# 002.net
KiCad netlist of a schematic drawn in EAGLE
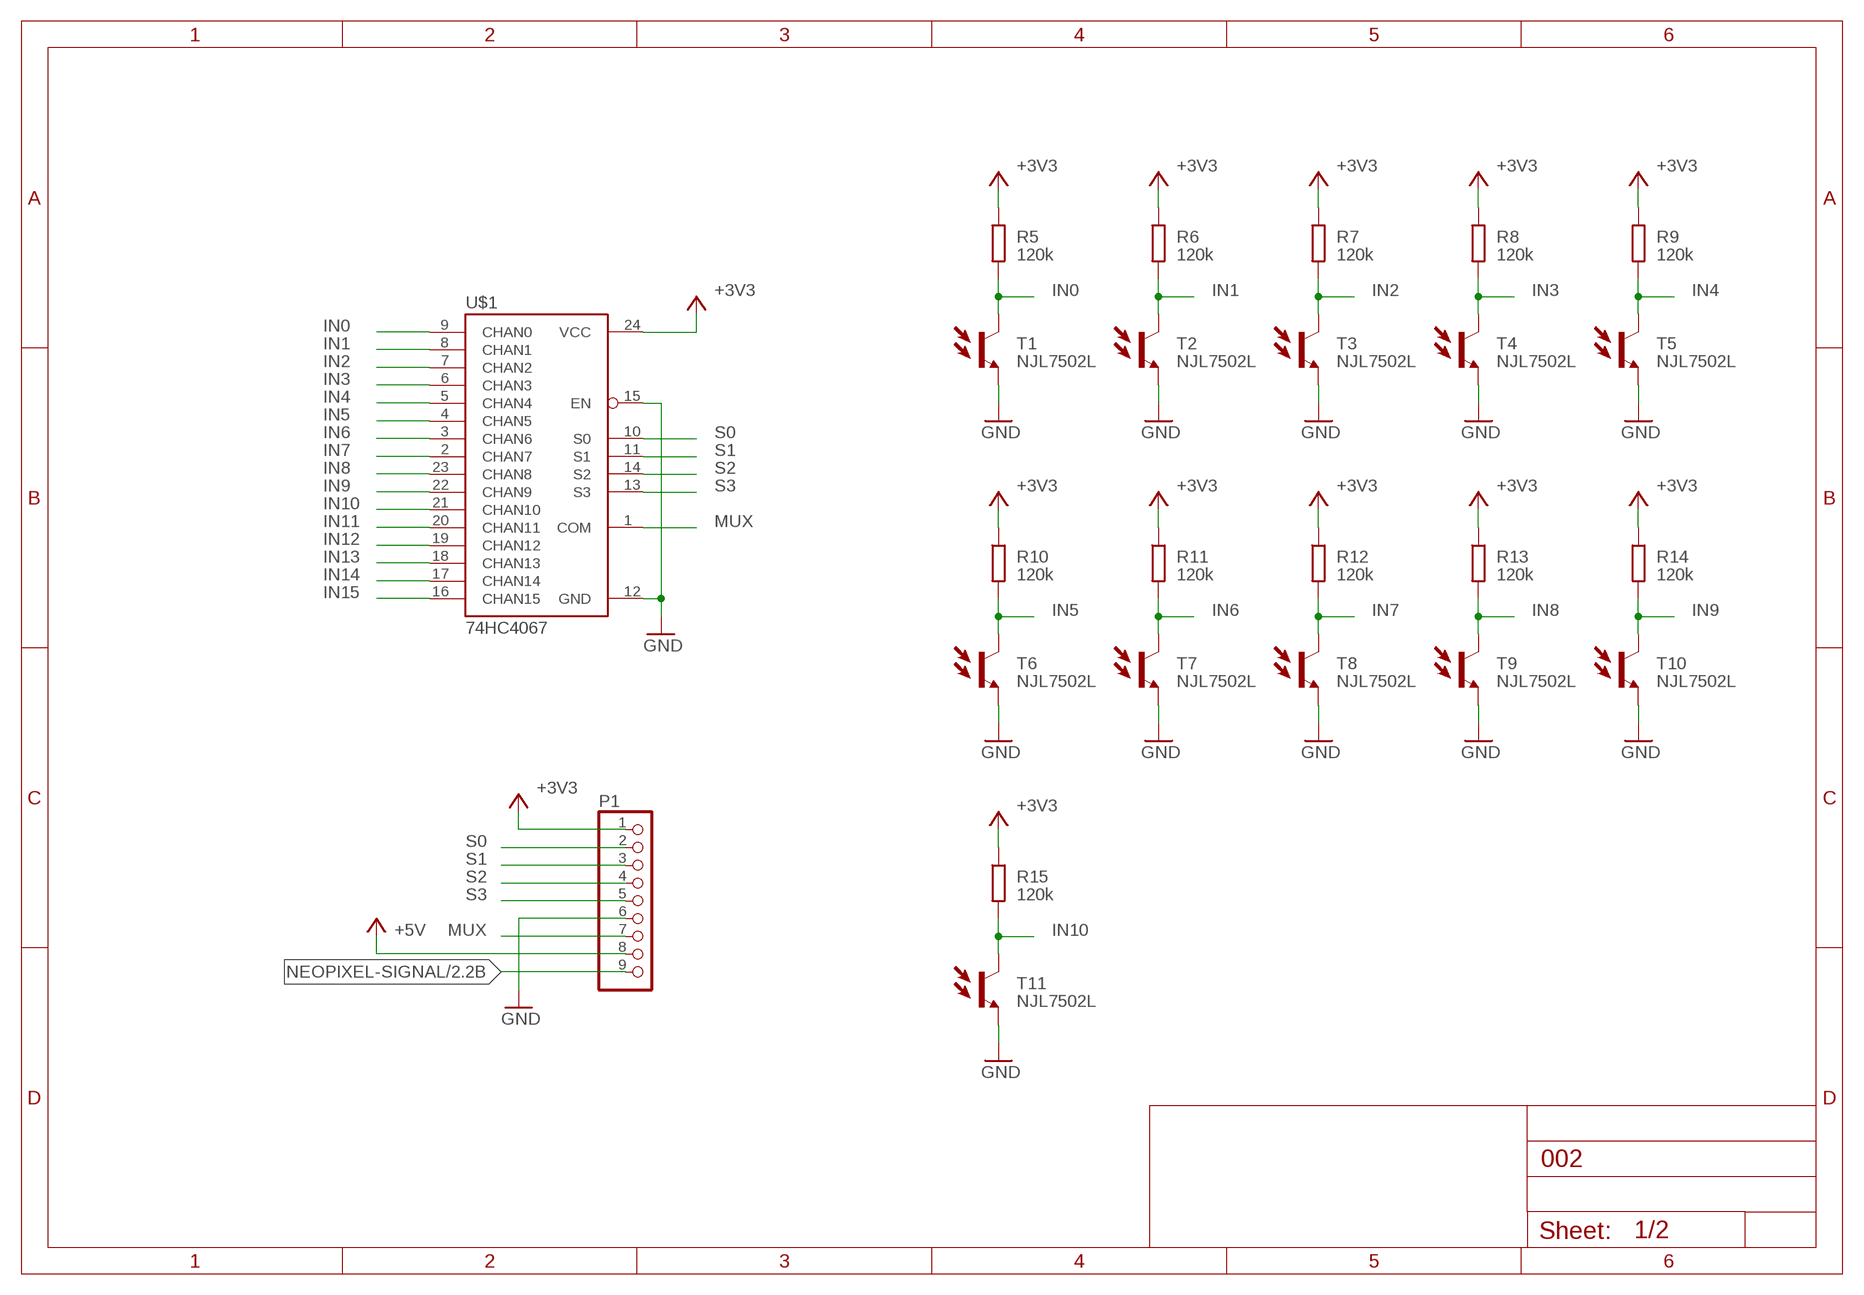
[diagram p0: schematic, sheet 1]
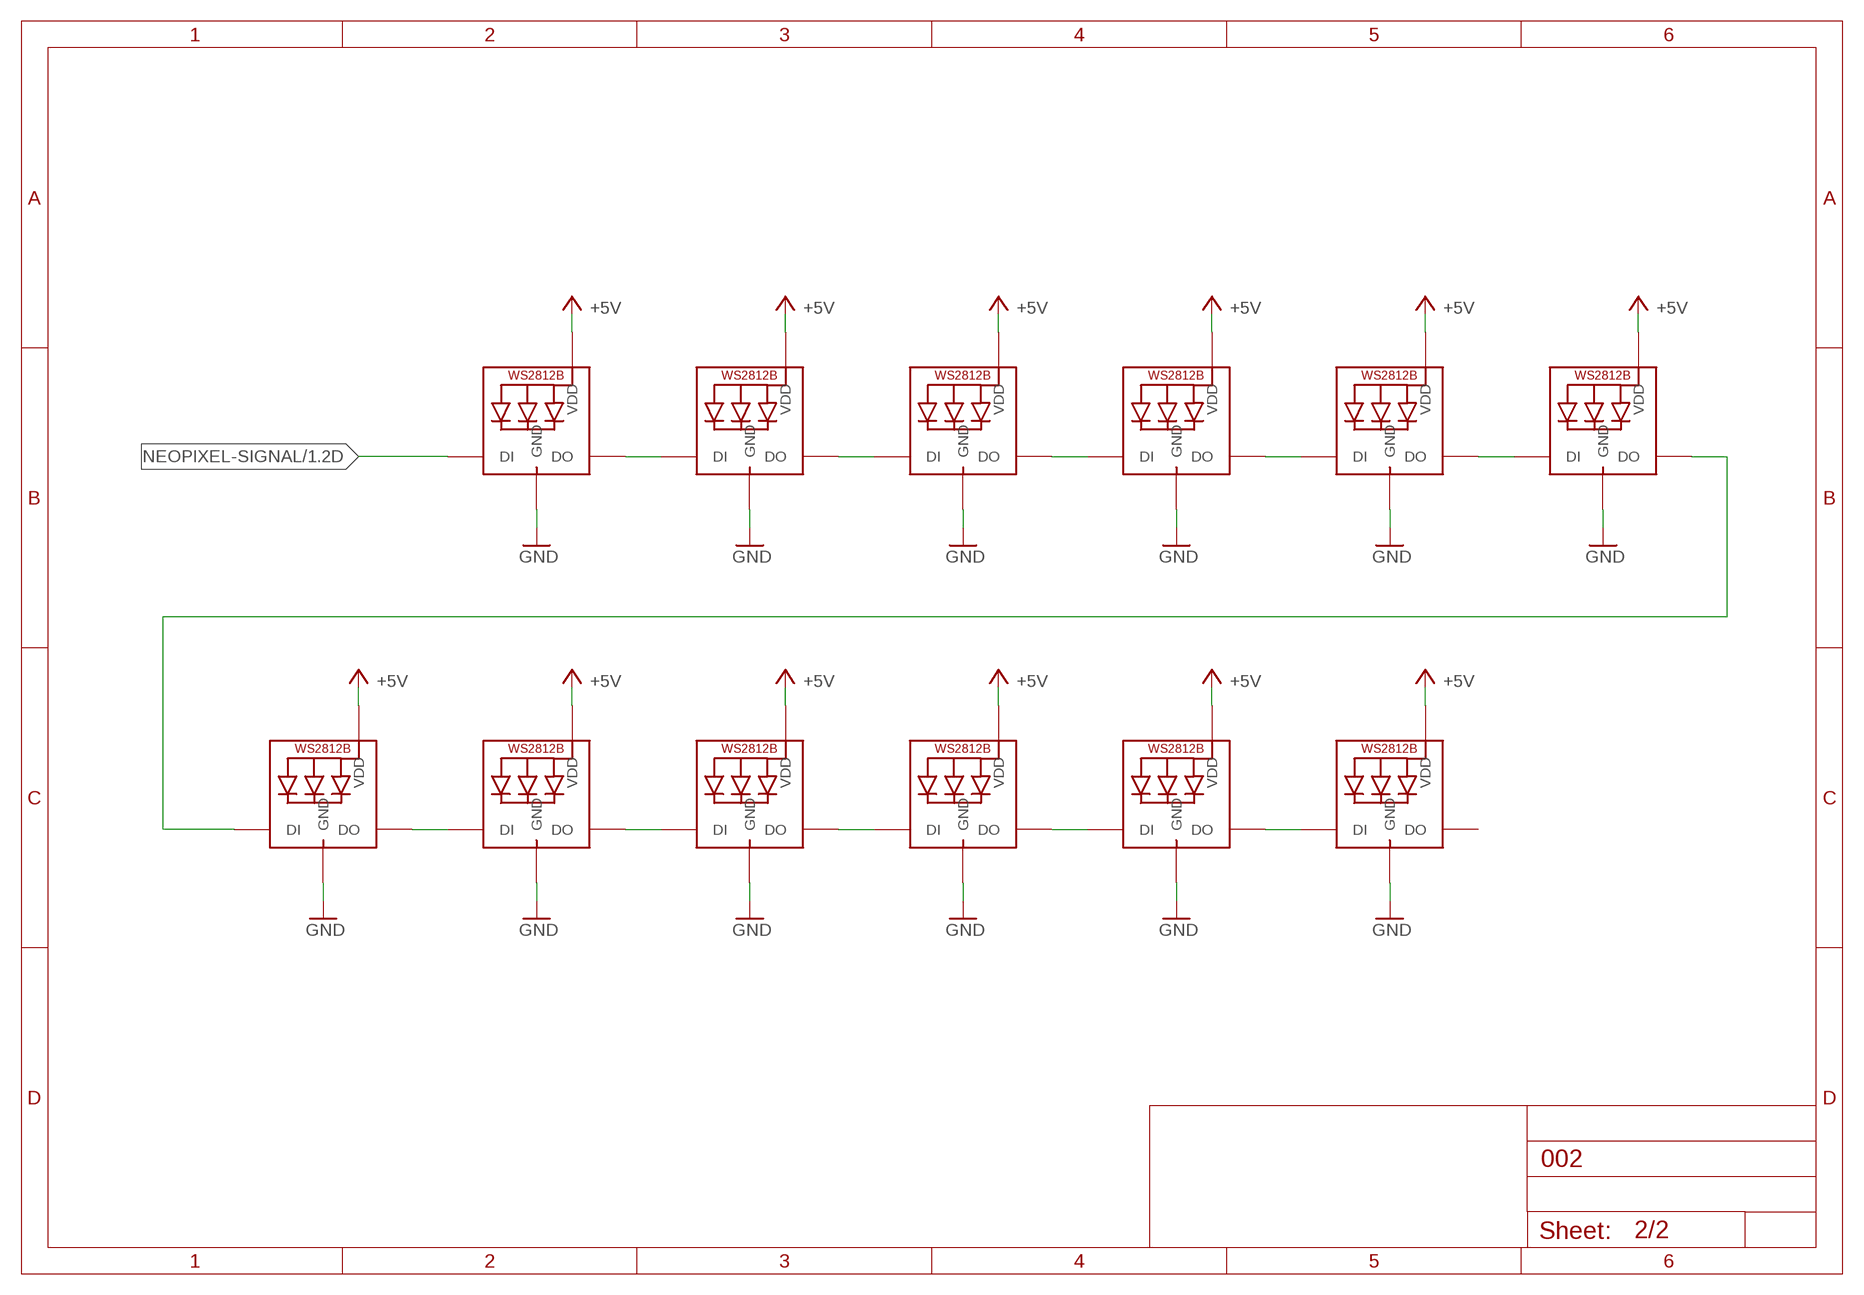
[diagram p1: schematic, sheet 2]

(export (version "E")
  (design (tool "Eeschema 10.0.6"))
  (components
    (comp (ref "LED1")
      (value "WS2812B5050")
      (footprint "eagle-import:WS2812B")
      (libsource (lib "eagle-import") (part "WS2812B5050"))
    )
    (comp (ref "LED2")
      (value "WS2812B5050")
      (footprint "eagle-import:WS2812B")
      (libsource (lib "eagle-import") (part "WS2812B5050"))
    )
    (comp (ref "LED3")
      (value "WS2812B5050")
      (footprint "eagle-import:WS2812B")
      (libsource (lib "eagle-import") (part "WS2812B5050"))
    )
    (comp (ref "LED4")
      (value "WS2812B5050")
      (footprint "eagle-import:WS2812B")
      (libsource (lib "eagle-import") (part "WS2812B5050"))
    )
    (comp (ref "LED5")
      (value "WS2812B5050")
      (footprint "eagle-import:WS2812B")
      (libsource (lib "eagle-import") (part "WS2812B5050"))
    )
    (comp (ref "LED6")
      (value "WS2812B5050")
      (footprint "eagle-import:WS2812B")
      (libsource (lib "eagle-import") (part "WS2812B5050"))
    )
    (comp (ref "LED7")
      (value "WS2812B5050")
      (footprint "eagle-import:WS2812B")
      (libsource (lib "eagle-import") (part "WS2812B5050"))
    )
    (comp (ref "LED8")
      (value "WS2812B5050")
      (footprint "eagle-import:WS2812B")
      (libsource (lib "eagle-import") (part "WS2812B5050"))
    )
    (comp (ref "LED9")
      (value "WS2812B5050")
      (footprint "eagle-import:WS2812B")
      (libsource (lib "eagle-import") (part "WS2812B5050"))
    )
    (comp (ref "LED10")
      (value "WS2812B5050")
      (footprint "eagle-import:WS2812B")
      (libsource (lib "eagle-import") (part "WS2812B5050"))
    )
    (comp (ref "LED11")
      (value "WS2812B5050")
      (footprint "eagle-import:WS2812B")
      (libsource (lib "eagle-import") (part "WS2812B5050"))
    )
    (comp (ref "LED12")
      (value "WS2812B5050")
      (footprint "eagle-import:WS2812B")
      (libsource (lib "eagle-import") (part "WS2812B5050"))
    )
    (comp (ref "P1")
      (value "S9B-ZR-SM4A-TF")
      (footprint "eagle-import:ZH-SM4-SIDE09")
      (libsource (lib "eagle-import") (part "S9B-ZR-SM4A-TF"))
    )
    (comp (ref "R5")
      (value "120k")
      (footprint "eagle-import:R0805")
      (libsource (lib "eagle-import") (part "R-EU_R0805"))
    )
    (comp (ref "R6")
      (value "120k")
      (footprint "eagle-import:R0805")
      (libsource (lib "eagle-import") (part "R-EU_R0805"))
    )
    (comp (ref "R7")
      (value "120k")
      (footprint "eagle-import:R0805")
      (libsource (lib "eagle-import") (part "R-EU_R0805"))
    )
    (comp (ref "R8")
      (value "120k")
      (footprint "eagle-import:R0805")
      (libsource (lib "eagle-import") (part "R-EU_R0805"))
    )
    (comp (ref "R9")
      (value "120k")
      (footprint "eagle-import:R0805")
      (libsource (lib "eagle-import") (part "R-EU_R0805"))
    )
    (comp (ref "R10")
      (value "120k")
      (footprint "eagle-import:R0805")
      (libsource (lib "eagle-import") (part "R-EU_R0805"))
    )
    (comp (ref "R11")
      (value "120k")
      (footprint "eagle-import:R0805")
      (libsource (lib "eagle-import") (part "R-EU_R0805"))
    )
    (comp (ref "R12")
      (value "120k")
      (footprint "eagle-import:R0805")
      (libsource (lib "eagle-import") (part "R-EU_R0805"))
    )
    (comp (ref "R13")
      (value "120k")
      (footprint "eagle-import:R0805")
      (libsource (lib "eagle-import") (part "R-EU_R0805"))
    )
    (comp (ref "R14")
      (value "120k")
      (footprint "eagle-import:R0805")
      (libsource (lib "eagle-import") (part "R-EU_R0805"))
    )
    (comp (ref "R15")
      (value "120k")
      (footprint "eagle-import:R0805")
      (libsource (lib "eagle-import") (part "R-EU_R0805"))
    )
    (comp (ref "T1")
      (value "NJL7502L")
      (footprint "eagle-import:MYPARTS_NJL7502L")
      (libsource (lib "eagle-import") (part "MYPARTS_NJL7502L"))
    )
    (comp (ref "T2")
      (value "NJL7502L")
      (footprint "eagle-import:MYPARTS_NJL7502L")
      (libsource (lib "eagle-import") (part "MYPARTS_NJL7502L"))
    )
    (comp (ref "T3")
      (value "NJL7502L")
      (footprint "eagle-import:MYPARTS_NJL7502L")
      (libsource (lib "eagle-import") (part "MYPARTS_NJL7502L"))
    )
    (comp (ref "T4")
      (value "NJL7502L")
      (footprint "eagle-import:MYPARTS_NJL7502L")
      (libsource (lib "eagle-import") (part "MYPARTS_NJL7502L"))
    )
    (comp (ref "T5")
      (value "NJL7502L")
      (footprint "eagle-import:MYPARTS_NJL7502L")
      (libsource (lib "eagle-import") (part "MYPARTS_NJL7502L"))
    )
    (comp (ref "T6")
      (value "NJL7502L")
      (footprint "eagle-import:MYPARTS_NJL7502L")
      (libsource (lib "eagle-import") (part "MYPARTS_NJL7502L"))
    )
    (comp (ref "T7")
      (value "NJL7502L")
      (footprint "eagle-import:MYPARTS_NJL7502L")
      (libsource (lib "eagle-import") (part "MYPARTS_NJL7502L"))
    )
    (comp (ref "T8")
      (value "NJL7502L")
      (footprint "eagle-import:MYPARTS_NJL7502L")
      (libsource (lib "eagle-import") (part "MYPARTS_NJL7502L"))
    )
    (comp (ref "T9")
      (value "NJL7502L")
      (footprint "eagle-import:MYPARTS_NJL7502L")
      (libsource (lib "eagle-import") (part "MYPARTS_NJL7502L"))
    )
    (comp (ref "T10")
      (value "NJL7502L")
      (footprint "eagle-import:MYPARTS_NJL7502L")
      (libsource (lib "eagle-import") (part "MYPARTS_NJL7502L"))
    )
    (comp (ref "T11")
      (value "NJL7502L")
      (footprint "eagle-import:MYPARTS_NJL7502L")
      (libsource (lib "eagle-import") (part "MYPARTS_NJL7502L"))
    )
    (comp (ref "U$1")
      (value "74HC4067")
      (footprint "eagle-import:SPARKFUN_SSOP24")
      (libsource (lib "eagle-import") (part "SPARKFUN_MUX-74HC4067SMD"))
    )
  )
  (nets
    (net (code "1") (name "+3V3") (class "Default")
      (node (ref "P1") (pin "1") (pinfunction "1_1") (pintype "passive"))
      (node (ref "R10") (pin "1") (pinfunction "1_1") (pintype "passive"))
      (node (ref "R11") (pin "1") (pinfunction "1_1") (pintype "passive"))
      (node (ref "R12") (pin "1") (pinfunction "1_1") (pintype "passive"))
      (node (ref "R13") (pin "1") (pinfunction "1_1") (pintype "passive"))
      (node (ref "R14") (pin "1") (pinfunction "1_1") (pintype "passive"))
      (node (ref "R15") (pin "1") (pinfunction "1_1") (pintype "passive"))
      (node (ref "R5") (pin "1") (pinfunction "1_1") (pintype "passive"))
      (node (ref "R6") (pin "1") (pinfunction "1_1") (pintype "passive"))
      (node (ref "R7") (pin "1") (pinfunction "1_1") (pintype "passive"))
      (node (ref "R8") (pin "1") (pinfunction "1_1") (pintype "passive"))
      (node (ref "R9") (pin "1") (pinfunction "1_1") (pintype "passive"))
      (node (ref "U$1") (pin "24") (pinfunction "VCC_24") (pintype "bidirectional"))
    )
    (net (code "2") (name "+5V") (class "Default")
      (node (ref "LED1") (pin "1-VDD") (pinfunction "VDD_1-VDD") (pintype "power_in"))
      (node (ref "LED10") (pin "1-VDD") (pinfunction "VDD_1-VDD") (pintype "power_in"))
      (node (ref "LED11") (pin "1-VDD") (pinfunction "VDD_1-VDD") (pintype "power_in"))
      (node (ref "LED12") (pin "1-VDD") (pinfunction "VDD_1-VDD") (pintype "power_in"))
      (node (ref "LED2") (pin "1-VDD") (pinfunction "VDD_1-VDD") (pintype "power_in"))
      (node (ref "LED3") (pin "1-VDD") (pinfunction "VDD_1-VDD") (pintype "power_in"))
      (node (ref "LED4") (pin "1-VDD") (pinfunction "VDD_1-VDD") (pintype "power_in"))
      (node (ref "LED5") (pin "1-VDD") (pinfunction "VDD_1-VDD") (pintype "power_in"))
      (node (ref "LED6") (pin "1-VDD") (pinfunction "VDD_1-VDD") (pintype "power_in"))
      (node (ref "LED7") (pin "1-VDD") (pinfunction "VDD_1-VDD") (pintype "power_in"))
      (node (ref "LED8") (pin "1-VDD") (pinfunction "VDD_1-VDD") (pintype "power_in"))
      (node (ref "LED9") (pin "1-VDD") (pinfunction "VDD_1-VDD") (pintype "power_in"))
      (node (ref "P1") (pin "8") (pinfunction "8_8") (pintype "passive"))
    )
    (net (code "3") (name "GND") (class "Default")
      (node (ref "LED1") (pin "3-GND") (pinfunction "GND_3-GND") (pintype "power_in"))
      (node (ref "LED10") (pin "3-GND") (pinfunction "GND_3-GND") (pintype "power_in"))
      (node (ref "LED11") (pin "3-GND") (pinfunction "GND_3-GND") (pintype "power_in"))
      (node (ref "LED12") (pin "3-GND") (pinfunction "GND_3-GND") (pintype "power_in"))
      (node (ref "LED2") (pin "3-GND") (pinfunction "GND_3-GND") (pintype "power_in"))
      (node (ref "LED3") (pin "3-GND") (pinfunction "GND_3-GND") (pintype "power_in"))
      (node (ref "LED4") (pin "3-GND") (pinfunction "GND_3-GND") (pintype "power_in"))
      (node (ref "LED5") (pin "3-GND") (pinfunction "GND_3-GND") (pintype "power_in"))
      (node (ref "LED6") (pin "3-GND") (pinfunction "GND_3-GND") (pintype "power_in"))
      (node (ref "LED7") (pin "3-GND") (pinfunction "GND_3-GND") (pintype "power_in"))
      (node (ref "LED8") (pin "3-GND") (pinfunction "GND_3-GND") (pintype "power_in"))
      (node (ref "LED9") (pin "3-GND") (pinfunction "GND_3-GND") (pintype "power_in"))
      (node (ref "P1") (pin "6") (pinfunction "6_6") (pintype "passive"))
      (node (ref "T1") (pin "E") (pinfunction "E_E") (pintype "passive"))
      (node (ref "T10") (pin "E") (pinfunction "E_E") (pintype "passive"))
      (node (ref "T11") (pin "E") (pinfunction "E_E") (pintype "passive"))
      (node (ref "T2") (pin "E") (pinfunction "E_E") (pintype "passive"))
      (node (ref "T3") (pin "E") (pinfunction "E_E") (pintype "passive"))
      (node (ref "T4") (pin "E") (pinfunction "E_E") (pintype "passive"))
      (node (ref "T5") (pin "E") (pinfunction "E_E") (pintype "passive"))
      (node (ref "T6") (pin "E") (pinfunction "E_E") (pintype "passive"))
      (node (ref "T7") (pin "E") (pinfunction "E_E") (pintype "passive"))
      (node (ref "T8") (pin "E") (pinfunction "E_E") (pintype "passive"))
      (node (ref "T9") (pin "E") (pinfunction "E_E") (pintype "passive"))
      (node (ref "U$1") (pin "12") (pinfunction "GND_12") (pintype "bidirectional"))
      (node (ref "U$1") (pin "15") (pinfunction "EN_15") (pintype "input"))
    )
    (net (code "4") (name "IN0") (class "Default")
      (node (ref "R5") (pin "2") (pinfunction "2_2") (pintype "passive"))
      (node (ref "T1") (pin "C") (pinfunction "C_C") (pintype "passive"))
      (node (ref "U$1") (pin "9") (pinfunction "CHAN0_9") (pintype "bidirectional"))
    )
    (net (code "5") (name "IN1") (class "Default")
      (node (ref "R6") (pin "2") (pinfunction "2_2") (pintype "passive"))
      (node (ref "T2") (pin "C") (pinfunction "C_C") (pintype "passive"))
      (node (ref "U$1") (pin "8") (pinfunction "CHAN1_8") (pintype "bidirectional"))
    )
    (net (code "6") (name "IN2") (class "Default")
      (node (ref "R7") (pin "2") (pinfunction "2_2") (pintype "passive"))
      (node (ref "T3") (pin "C") (pinfunction "C_C") (pintype "passive"))
      (node (ref "U$1") (pin "7") (pinfunction "CHAN2_7") (pintype "bidirectional"))
    )
    (net (code "7") (name "IN3") (class "Default")
      (node (ref "R8") (pin "2") (pinfunction "2_2") (pintype "passive"))
      (node (ref "T4") (pin "C") (pinfunction "C_C") (pintype "passive"))
      (node (ref "U$1") (pin "6") (pinfunction "CHAN3_6") (pintype "bidirectional"))
    )
    (net (code "8") (name "IN4") (class "Default")
      (node (ref "R9") (pin "2") (pinfunction "2_2") (pintype "passive"))
      (node (ref "T5") (pin "C") (pinfunction "C_C") (pintype "passive"))
      (node (ref "U$1") (pin "5") (pinfunction "CHAN4_5") (pintype "bidirectional"))
    )
    (net (code "9") (name "IN5") (class "Default")
      (node (ref "R10") (pin "2") (pinfunction "2_2") (pintype "passive"))
      (node (ref "T6") (pin "C") (pinfunction "C_C") (pintype "passive"))
      (node (ref "U$1") (pin "4") (pinfunction "CHAN5_4") (pintype "bidirectional"))
    )
    (net (code "10") (name "IN6") (class "Default")
      (node (ref "R11") (pin "2") (pinfunction "2_2") (pintype "passive"))
      (node (ref "T7") (pin "C") (pinfunction "C_C") (pintype "passive"))
      (node (ref "U$1") (pin "3") (pinfunction "CHAN6_3") (pintype "bidirectional"))
    )
    (net (code "11") (name "IN7") (class "Default")
      (node (ref "R12") (pin "2") (pinfunction "2_2") (pintype "passive"))
      (node (ref "T8") (pin "C") (pinfunction "C_C") (pintype "passive"))
      (node (ref "U$1") (pin "2") (pinfunction "CHAN7_2") (pintype "bidirectional"))
    )
    (net (code "12") (name "IN8") (class "Default")
      (node (ref "R13") (pin "2") (pinfunction "2_2") (pintype "passive"))
      (node (ref "T9") (pin "C") (pinfunction "C_C") (pintype "passive"))
      (node (ref "U$1") (pin "23") (pinfunction "CHAN8_23") (pintype "bidirectional"))
    )
    (net (code "13") (name "IN9") (class "Default")
      (node (ref "R14") (pin "2") (pinfunction "2_2") (pintype "passive"))
      (node (ref "T10") (pin "C") (pinfunction "C_C") (pintype "passive"))
      (node (ref "U$1") (pin "22") (pinfunction "CHAN9_22") (pintype "bidirectional"))
    )
    (net (code "14") (name "IN10") (class "Default")
      (node (ref "R15") (pin "2") (pinfunction "2_2") (pintype "passive"))
      (node (ref "T11") (pin "C") (pinfunction "C_C") (pintype "passive"))
      (node (ref "U$1") (pin "21") (pinfunction "CHAN10_21") (pintype "bidirectional"))
    )
    (net (code "15") (name "IN11") (class "Default")
      (node (ref "U$1") (pin "20") (pinfunction "CHAN11_20") (pintype "bidirectional"))
    )
    (net (code "16") (name "IN12") (class "Default")
      (node (ref "U$1") (pin "19") (pinfunction "CHAN12_19") (pintype "bidirectional"))
    )
    (net (code "17") (name "IN13") (class "Default")
      (node (ref "U$1") (pin "18") (pinfunction "CHAN13_18") (pintype "bidirectional"))
    )
    (net (code "18") (name "IN14") (class "Default")
      (node (ref "U$1") (pin "17") (pinfunction "CHAN14_17") (pintype "bidirectional"))
    )
    (net (code "19") (name "IN15") (class "Default")
      (node (ref "U$1") (pin "16") (pinfunction "CHAN15_16") (pintype "bidirectional"))
    )
    (net (code "20") (name "MUX") (class "Default")
      (node (ref "P1") (pin "7") (pinfunction "7_7") (pintype "passive"))
      (node (ref "U$1") (pin "1") (pinfunction "COM_1") (pintype "bidirectional"))
    )
    (net (code "21") (name "NEOPIXEL-SIGNAL") (class "Default")
      (node (ref "LED1") (pin "4-DIN") (pinfunction "DI_4-DIN") (pintype "input"))
      (node (ref "P1") (pin "9") (pinfunction "9_9") (pintype "passive"))
    )
    (net (code "22") (name "Net-(LED1-DO)") (class "Default")
      (node (ref "LED1") (pin "2-DOUT") (pinfunction "DO_2-DOUT") (pintype "output"))
      (node (ref "LED2") (pin "4-DIN") (pinfunction "DI_4-DIN") (pintype "input"))
    )
    (net (code "23") (name "Net-(LED2-DO)") (class "Default")
      (node (ref "LED2") (pin "2-DOUT") (pinfunction "DO_2-DOUT") (pintype "output"))
      (node (ref "LED3") (pin "4-DIN") (pinfunction "DI_4-DIN") (pintype "input"))
    )
    (net (code "24") (name "Net-(LED3-DO)") (class "Default")
      (node (ref "LED3") (pin "2-DOUT") (pinfunction "DO_2-DOUT") (pintype "output"))
      (node (ref "LED4") (pin "4-DIN") (pinfunction "DI_4-DIN") (pintype "input"))
    )
    (net (code "25") (name "Net-(LED4-DO)") (class "Default")
      (node (ref "LED4") (pin "2-DOUT") (pinfunction "DO_2-DOUT") (pintype "output"))
      (node (ref "LED5") (pin "4-DIN") (pinfunction "DI_4-DIN") (pintype "input"))
    )
    (net (code "26") (name "Net-(LED5-DO)") (class "Default")
      (node (ref "LED5") (pin "2-DOUT") (pinfunction "DO_2-DOUT") (pintype "output"))
      (node (ref "LED6") (pin "4-DIN") (pinfunction "DI_4-DIN") (pintype "input"))
    )
    (net (code "27") (name "Net-(LED6-DO)") (class "Default")
      (node (ref "LED6") (pin "2-DOUT") (pinfunction "DO_2-DOUT") (pintype "output"))
      (node (ref "LED7") (pin "4-DIN") (pinfunction "DI_4-DIN") (pintype "input"))
    )
    (net (code "28") (name "Net-(LED7-DO)") (class "Default")
      (node (ref "LED7") (pin "2-DOUT") (pinfunction "DO_2-DOUT") (pintype "output"))
      (node (ref "LED8") (pin "4-DIN") (pinfunction "DI_4-DIN") (pintype "input"))
    )
    (net (code "29") (name "Net-(LED8-DO)") (class "Default")
      (node (ref "LED8") (pin "2-DOUT") (pinfunction "DO_2-DOUT") (pintype "output"))
      (node (ref "LED9") (pin "4-DIN") (pinfunction "DI_4-DIN") (pintype "input"))
    )
    (net (code "30") (name "Net-(LED10-DI)") (class "Default")
      (node (ref "LED10") (pin "4-DIN") (pinfunction "DI_4-DIN") (pintype "input"))
      (node (ref "LED9") (pin "2-DOUT") (pinfunction "DO_2-DOUT") (pintype "output"))
    )
    (net (code "31") (name "Net-(LED10-DO)") (class "Default")
      (node (ref "LED10") (pin "2-DOUT") (pinfunction "DO_2-DOUT") (pintype "output"))
      (node (ref "LED11") (pin "4-DIN") (pinfunction "DI_4-DIN") (pintype "input"))
    )
    (net (code "32") (name "Net-(LED11-DO)") (class "Default")
      (node (ref "LED11") (pin "2-DOUT") (pinfunction "DO_2-DOUT") (pintype "output"))
      (node (ref "LED12") (pin "4-DIN") (pinfunction "DI_4-DIN") (pintype "input"))
    )
    (net (code "33") (name "S0") (class "Default")
      (node (ref "P1") (pin "2") (pinfunction "2_2") (pintype "passive"))
      (node (ref "U$1") (pin "10") (pinfunction "S0_10") (pintype "input"))
    )
    (net (code "34") (name "S1") (class "Default")
      (node (ref "P1") (pin "3") (pinfunction "3_3") (pintype "passive"))
      (node (ref "U$1") (pin "11") (pinfunction "S1_11") (pintype "input"))
    )
    (net (code "35") (name "S2") (class "Default")
      (node (ref "P1") (pin "4") (pinfunction "4_4") (pintype "passive"))
      (node (ref "U$1") (pin "14") (pinfunction "S2_14") (pintype "input"))
    )
    (net (code "36") (name "S3") (class "Default")
      (node (ref "P1") (pin "5") (pinfunction "5_5") (pintype "passive"))
      (node (ref "U$1") (pin "13") (pinfunction "S3_13") (pintype "input"))
    )
    (net (code "37") (name "unconnected-(LED12-DO-Pad2-DOUT)") (class "Default")
      (node (ref "LED12") (pin "2-DOUT") (pinfunction "DO_2-DOUT") (pintype "output"))
    )
  )
)
